# camera_module.net
KiCad netlist of a schematic drawn in EAGLE
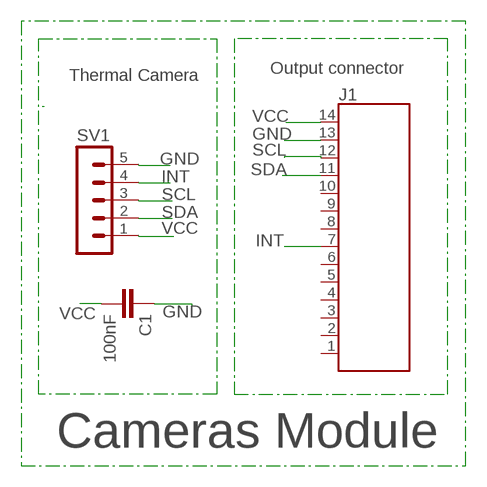
[diagram p0: schematic, sheet 1]

(export (version "E")
  (design (tool "Eeschema 10.0.6"))
  (components
    (comp (ref "C1")
      (value "100nF")
      (footprint "eagle-import:C0805")
      (libsource (lib "eagle-import") (part "C-EUC0805"))
    )
    (comp (ref "J1")
      (value "686114183522")
      (footprint "eagle-import:686114183522")
      (libsource (lib "eagle-import") (part "686114183522"))
    )
    (comp (ref "SV1")
      (value "MA05-1")
      (footprint "eagle-import:MA05-1")
      (libsource (lib "eagle-import") (part "MA05-1"))
    )
  )
  (nets
    (net (code "1") (name "/GND") (class "Default")
      (node (ref "C1") (pin "1") (pinfunction "1_1") (pintype "passive"))
      (node (ref "J1") (pin "13") (pinfunction "2_13") (pintype "passive"))
      (node (ref "SV1") (pin "5") (pinfunction "5_5") (pintype "passive"))
    )
    (net (code "2") (name "/INT") (class "Default")
      (node (ref "J1") (pin "7") (pinfunction "8_7") (pintype "passive"))
      (node (ref "SV1") (pin "4") (pinfunction "4_4") (pintype "passive"))
    )
    (net (code "3") (name "/SCL") (class "Default")
      (node (ref "J1") (pin "12") (pinfunction "3_12") (pintype "passive"))
      (node (ref "SV1") (pin "3") (pinfunction "3_3") (pintype "passive"))
    )
    (net (code "4") (name "/SDA") (class "Default")
      (node (ref "J1") (pin "11") (pinfunction "4_11") (pintype "passive"))
      (node (ref "SV1") (pin "2") (pinfunction "2_2") (pintype "passive"))
    )
    (net (code "5") (name "/VCC") (class "Default")
      (node (ref "C1") (pin "2") (pinfunction "2_2") (pintype "passive"))
      (node (ref "J1") (pin "14") (pinfunction "1_14") (pintype "passive"))
      (node (ref "SV1") (pin "1") (pinfunction "1_1") (pintype "passive"))
    )
    (net (code "6") (name "unconnected-(J1-5-Pad10)") (class "Default")
      (node (ref "J1") (pin "10") (pinfunction "5_10") (pintype "passive"))
    )
    (net (code "7") (name "unconnected-(J1-6-Pad9)") (class "Default")
      (node (ref "J1") (pin "9") (pinfunction "6_9") (pintype "passive"))
    )
    (net (code "8") (name "unconnected-(J1-7-Pad8)") (class "Default")
      (node (ref "J1") (pin "8") (pinfunction "7_8") (pintype "passive"))
    )
    (net (code "9") (name "unconnected-(J1-9-Pad6)") (class "Default")
      (node (ref "J1") (pin "6") (pinfunction "9_6") (pintype "passive"))
    )
    (net (code "10") (name "unconnected-(J1-10-Pad5)") (class "Default")
      (node (ref "J1") (pin "5") (pinfunction "10_5") (pintype "passive"))
    )
    (net (code "11") (name "unconnected-(J1-11-Pad4)") (class "Default")
      (node (ref "J1") (pin "4") (pinfunction "11_4") (pintype "passive"))
    )
    (net (code "12") (name "unconnected-(J1-12-Pad3)") (class "Default")
      (node (ref "J1") (pin "3") (pinfunction "12_3") (pintype "passive"))
    )
    (net (code "13") (name "unconnected-(J1-13-Pad2)") (class "Default")
      (node (ref "J1") (pin "2") (pinfunction "13_2") (pintype "passive"))
    )
    (net (code "14") (name "unconnected-(J1-14-Pad1)") (class "Default")
      (node (ref "J1") (pin "1") (pinfunction "14_1") (pintype "passive"))
    )
  )
)
